# touch-switch-controller.net
KiCad netlist of a schematic drawn in EAGLE
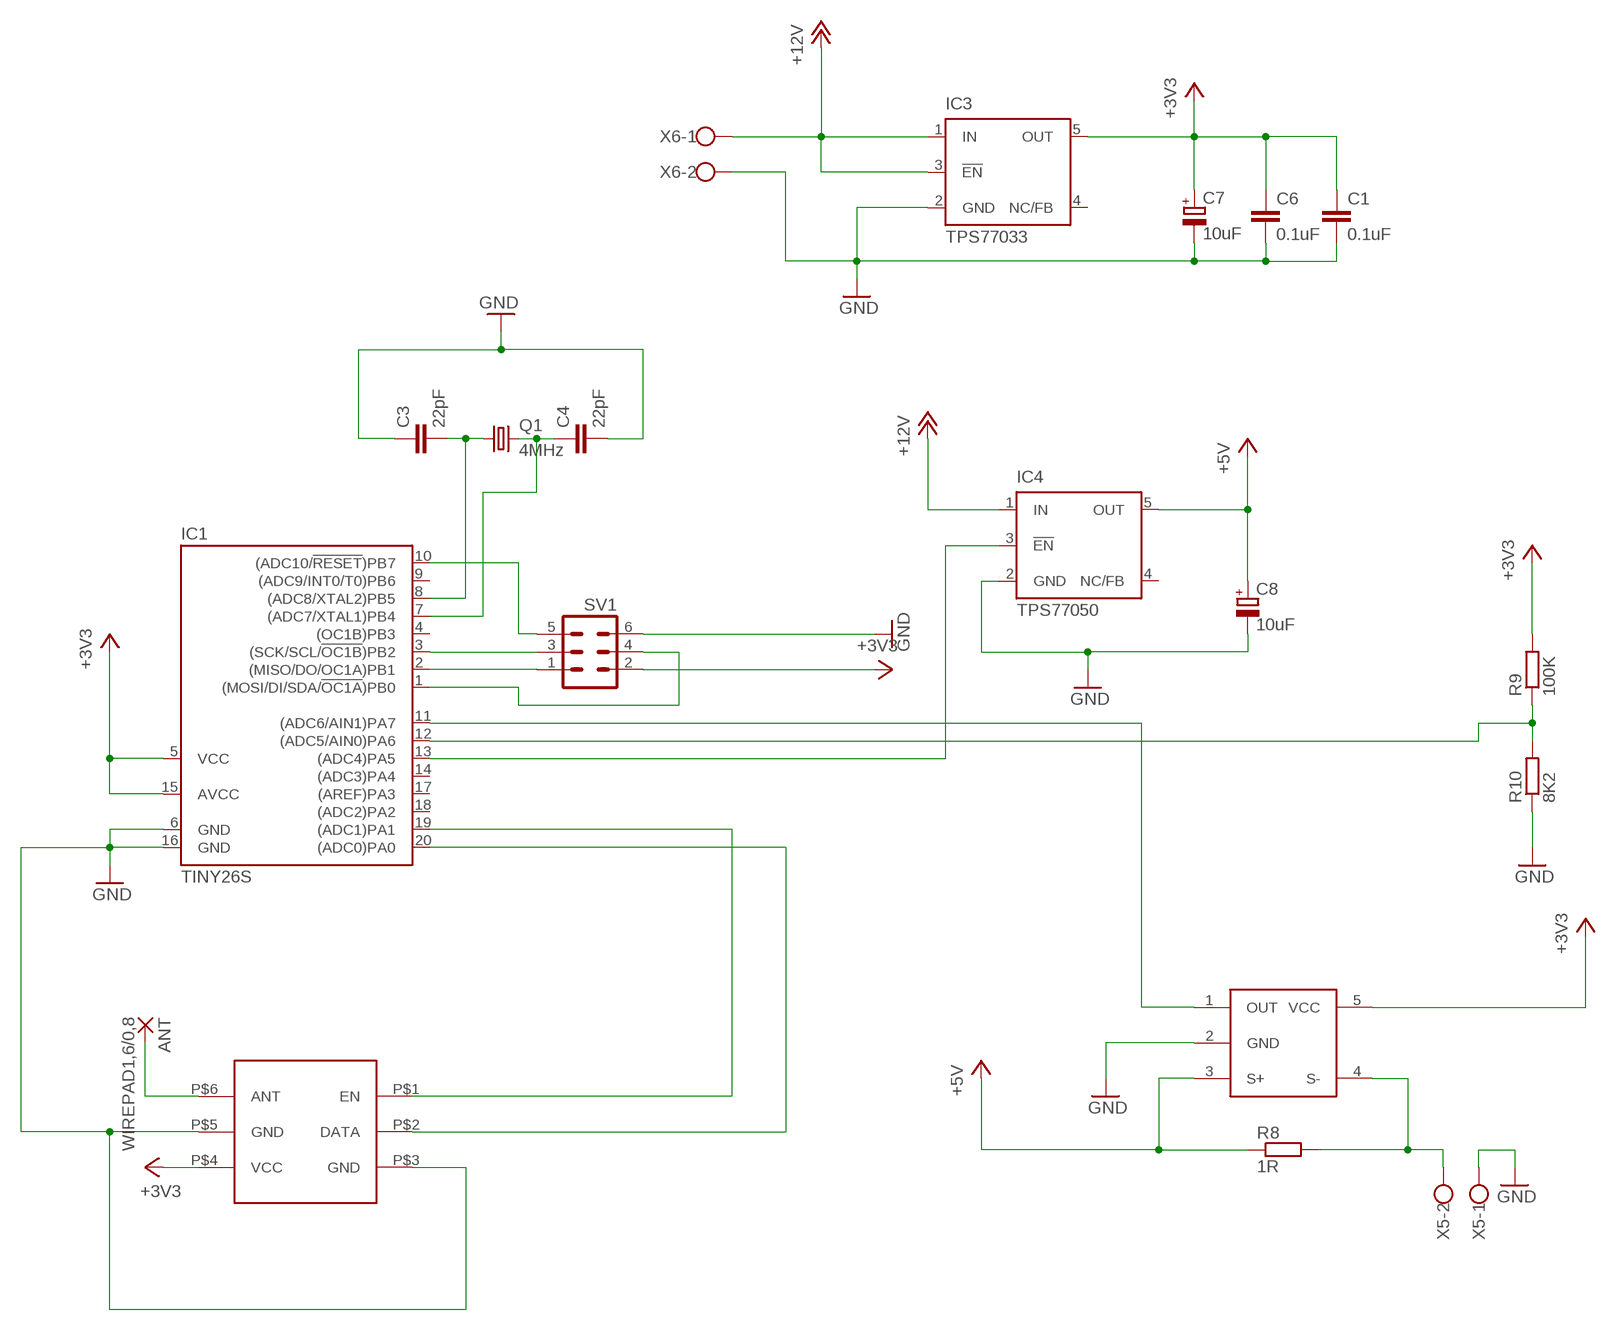
[diagram p0: schematic, sheet 1]

(export (version "E")
  (design (tool "Eeschema 10.0.6"))
  (components
    (comp (ref "ANT")
      (value "WIREPAD1,6/0,8")
      (footprint "eagle-import:1,6_0,8")
      (libsource (lib "eagle-import") (part "WIREPAD1,6/0,8"))
    )
    (comp (ref "C1")
      (value "0.1uF")
      (footprint "eagle-import:C0603")
      (libsource (lib "eagle-import") (part "C-EUC0603"))
    )
    (comp (ref "C3")
      (value "22pF")
      (footprint "eagle-import:C0603")
      (libsource (lib "eagle-import") (part "C-EUC0603"))
    )
    (comp (ref "C4")
      (value "22pF")
      (footprint "eagle-import:C0603")
      (libsource (lib "eagle-import") (part "C-EUC0603"))
    )
    (comp (ref "C6")
      (value "0.1uF")
      (footprint "eagle-import:C0603")
      (libsource (lib "eagle-import") (part "C-EUC0603"))
    )
    (comp (ref "C7")
      (value "10uF")
      (footprint "eagle-import:SMC_B")
      (libsource (lib "eagle-import") (part "CPOL-EUSMCB"))
    )
    (comp (ref "C8")
      (value "10uF")
      (footprint "eagle-import:SMC_B")
      (libsource (lib "eagle-import") (part "CPOL-EUSMCB"))
    )
    (comp (ref "IC1")
      (value "TINY26S")
      (footprint "eagle-import:SO20L")
      (fields (field (name "MPN") "ATTINY261-20SU"))
      (libsource (lib "eagle-import") (part "TINY26S"))
    )
    (comp (ref "IC3")
      (value "TPS77033")
      (footprint "eagle-import:SOT23-DBV")
      (fields (field (name "MF") "TEXAS INSTRUMENTS") (field (name "MPN") "TPS77033DBVT"))
      (libsource (lib "eagle-import") (part "TPS77033"))
    )
    (comp (ref "IC4")
      (value "TPS77050")
      (footprint "eagle-import:SOT23-DBV")
      (fields (field (name "MF") "TEXAS INSTRUMENT CONNECTORS") (field (name "MPN") "TPS77050DBVT"))
      (libsource (lib "eagle-import") (part "TPS77050"))
    )
    (comp (ref "Q1")
      (value "4MHz")
      (footprint "eagle-import:HC49UP")
      (libsource (lib "eagle-import") (part "CRYSTALHC49UP"))
    )
    (comp (ref "R8")
      (value "1R")
      (footprint "eagle-import:R0603")
      (libsource (lib "eagle-import") (part "R-EU_R0603"))
    )
    (comp (ref "R9")
      (value "100K")
      (footprint "eagle-import:R0603")
      (libsource (lib "eagle-import") (part "R-EU_R0603"))
    )
    (comp (ref "R10")
      (value "8K2")
      (footprint "eagle-import:R0603")
      (libsource (lib "eagle-import") (part "R-EU_R0603"))
    )
    (comp (ref "SV1")
      (value "MA03-2")
      (footprint "eagle-import:MA03-2")
      (libsource (lib "eagle-import") (part "MA03-2"))
    )
    (comp (ref "U$1")
      (value "ZXCT1086")
      (footprint "eagle-import:SOT23-5L")
      (libsource (lib "eagle-import") (part "ZXCT1086"))
    )
    (comp (ref "U$2")
      (value "RTFQ1")
      (footprint "eagle-import:RTFQ1")
      (libsource (lib "eagle-import") (part "RTFQ1"))
    )
    (comp (ref "X5")
      (value "W237-102")
      (footprint "eagle-import:W237-102")
      (fields (field (name "MPN") "237-102"))
      (libsource (lib "eagle-import") (part "W237-102"))
    )
    (comp (ref "X6")
      (value "W237-102")
      (footprint "eagle-import:W237-102")
      (fields (field (name "MPN") "237-102"))
      (libsource (lib "eagle-import") (part "W237-102"))
    )
  )
  (nets
    (net (code "1") (name "+3V3") (class "Default")
      (node (ref "C1") (pin "1") (pinfunction "1_1") (pintype "passive"))
      (node (ref "C6") (pin "1") (pinfunction "1_1") (pintype "passive"))
      (node (ref "C7") (pin "+") (pinfunction "+_+") (pintype "passive"))
      (node (ref "IC1") (pin "15") (pinfunction "AVCC_15") (pintype "power_in"))
      (node (ref "IC1") (pin "5") (pinfunction "VCC_5") (pintype "power_in"))
      (node (ref "IC3") (pin "5") (pinfunction "OUT_5") (pintype "passive"))
      (node (ref "R9") (pin "2") (pinfunction "2_2") (pintype "passive"))
      (node (ref "SV1") (pin "2") (pinfunction "2_2") (pintype "passive"))
      (node (ref "U$1") (pin "5") (pinfunction "VCC_5") (pintype "bidirectional"))
      (node (ref "U$2") (pin "P$4") (pinfunction "VCC_P$4") (pintype "bidirectional"))
    )
    (net (code "2") (name "+5V") (class "Default")
      (node (ref "C8") (pin "+") (pinfunction "+_+") (pintype "passive"))
      (node (ref "IC4") (pin "5") (pinfunction "OUT_5") (pintype "passive"))
      (node (ref "R8") (pin "1") (pinfunction "1_1") (pintype "passive"))
      (node (ref "U$1") (pin "3") (pinfunction "S+_3") (pintype "bidirectional"))
    )
    (net (code "3") (name "+12V") (class "Default")
      (node (ref "IC3") (pin "1") (pinfunction "IN_1") (pintype "input"))
      (node (ref "IC3") (pin "3") (pinfunction "~{EN}_3") (pintype "input"))
      (node (ref "IC4") (pin "1") (pinfunction "IN_1") (pintype "input"))
      (node (ref "X6") (pin "1") (pinfunction "KL_1") (pintype "passive"))
    )
    (net (code "4") (name "GND") (class "Default")
      (node (ref "C1") (pin "2") (pinfunction "2_2") (pintype "passive"))
      (node (ref "C3") (pin "1") (pinfunction "1_1") (pintype "passive"))
      (node (ref "C4") (pin "2") (pinfunction "2_2") (pintype "passive"))
      (node (ref "C6") (pin "2") (pinfunction "2_2") (pintype "passive"))
      (node (ref "C7") (pin "-") (pinfunction "-_-") (pintype "passive"))
      (node (ref "C8") (pin "-") (pinfunction "-_-") (pintype "passive"))
      (node (ref "IC1") (pin "16") (pinfunction "GND_16") (pintype "power_in"))
      (node (ref "IC1") (pin "6") (pinfunction "GND_6") (pintype "power_in"))
      (node (ref "IC3") (pin "2") (pinfunction "GND_2") (pintype "power_in"))
      (node (ref "IC4") (pin "2") (pinfunction "GND_2") (pintype "power_in"))
      (node (ref "R10") (pin "1") (pinfunction "1_1") (pintype "passive"))
      (node (ref "SV1") (pin "6") (pinfunction "6_6") (pintype "passive"))
      (node (ref "U$1") (pin "2") (pinfunction "GND_2") (pintype "bidirectional"))
      (node (ref "U$2") (pin "P$3") (pinfunction "GND_P$3") (pintype "bidirectional"))
      (node (ref "U$2") (pin "P$5") (pinfunction "GND_P$5") (pintype "bidirectional"))
      (node (ref "X5") (pin "1") (pinfunction "KL_1") (pintype "passive"))
      (node (ref "X6") (pin "2") (pinfunction "KL_2") (pintype "passive"))
    )
    (net (code "5") (name "Net-(ANT-P)") (class "Default")
      (node (ref "ANT") (pin "1") (pinfunction "P_1") (pintype "passive"))
      (node (ref "U$2") (pin "P$6") (pinfunction "ANT_P$6") (pintype "bidirectional"))
    )
    (net (code "6") (name "Net-(IC1-(ADC0)PA0)") (class "Default")
      (node (ref "IC1") (pin "20") (pinfunction "(ADC0)PA0_20") (pintype "bidirectional"))
      (node (ref "U$2") (pin "P$2") (pinfunction "DATA_P$2") (pintype "bidirectional"))
    )
    (net (code "7") (name "Net-(IC1-(ADC1)PA1)") (class "Default")
      (node (ref "IC1") (pin "19") (pinfunction "(ADC1)PA1_19") (pintype "bidirectional"))
      (node (ref "U$2") (pin "P$1") (pinfunction "EN_P$1") (pintype "bidirectional"))
    )
    (net (code "8") (name "Net-(IC1-(ADC4)PA5)") (class "Default")
      (node (ref "IC1") (pin "13") (pinfunction "(ADC4)PA5_13") (pintype "bidirectional"))
      (node (ref "IC4") (pin "3") (pinfunction "~{EN}_3") (pintype "input"))
    )
    (net (code "9") (name "Net-(IC1-(ADC5{slash}AIN0)PA6)") (class "Default")
      (node (ref "IC1") (pin "12") (pinfunction "(ADC5/AIN0)PA6_12") (pintype "bidirectional"))
      (node (ref "R10") (pin "2") (pinfunction "2_2") (pintype "passive"))
      (node (ref "R9") (pin "1") (pinfunction "1_1") (pintype "passive"))
    )
    (net (code "10") (name "Net-(IC1-(ADC6{slash}AIN1)PA7)") (class "Default")
      (node (ref "IC1") (pin "11") (pinfunction "(ADC6/AIN1)PA7_11") (pintype "bidirectional"))
      (node (ref "U$1") (pin "1") (pinfunction "OUT_1") (pintype "bidirectional"))
    )
    (net (code "11") (name "Net-(IC1-(ADC7{slash}XTAL1)PB4)") (class "Default")
      (node (ref "C4") (pin "1") (pinfunction "1_1") (pintype "passive"))
      (node (ref "IC1") (pin "7") (pinfunction "(ADC7/XTAL1)PB4_7") (pintype "bidirectional"))
      (node (ref "Q1") (pin "2") (pinfunction "2_2") (pintype "passive"))
    )
    (net (code "12") (name "Net-(IC1-(ADC8{slash}XTAL2)PB5)") (class "Default")
      (node (ref "C3") (pin "2") (pinfunction "2_2") (pintype "passive"))
      (node (ref "IC1") (pin "8") (pinfunction "(ADC8/XTAL2)PB5_8") (pintype "bidirectional"))
      (node (ref "Q1") (pin "1") (pinfunction "1_1") (pintype "passive"))
    )
    (net (code "13") (name "Net-(IC1-(ADC10{slash}~{RESET})PB7)") (class "Default")
      (node (ref "IC1") (pin "10") (pinfunction "(ADC10/~{RESET})PB7_10") (pintype "bidirectional"))
      (node (ref "SV1") (pin "5") (pinfunction "5_5") (pintype "passive"))
    )
    (net (code "14") (name "Net-(IC1-(MISO{slash}DO{slash}OC1A)PB1)") (class "Default")
      (node (ref "IC1") (pin "2") (pinfunction "(MISO/DO/OC1A)PB1_2") (pintype "bidirectional"))
      (node (ref "SV1") (pin "1") (pinfunction "1_1") (pintype "passive"))
    )
    (net (code "15") (name "Net-(IC1-(MOSI{slash}DI{slash}SDA{slash}~{OC1A})PB0)") (class "Default")
      (node (ref "IC1") (pin "1") (pinfunction "(MOSI/DI/SDA/~{OC1A})PB0_1") (pintype "bidirectional"))
      (node (ref "SV1") (pin "4") (pinfunction "4_4") (pintype "passive"))
    )
    (net (code "16") (name "Net-(IC1-(SCK{slash}SCL{slash}~{OC1B})PB2)") (class "Default")
      (node (ref "IC1") (pin "3") (pinfunction "(SCK/SCL/~{OC1B})PB2_3") (pintype "bidirectional"))
      (node (ref "SV1") (pin "3") (pinfunction "3_3") (pintype "passive"))
    )
    (net (code "17") (name "Net-(U$1-S-)") (class "Default")
      (node (ref "R8") (pin "2") (pinfunction "2_2") (pintype "passive"))
      (node (ref "U$1") (pin "4") (pinfunction "S-_4") (pintype "bidirectional"))
      (node (ref "X5") (pin "2") (pinfunction "KL_2") (pintype "passive"))
    )
    (net (code "18") (name "unconnected-(IC1-(ADC2)PA2-Pad18)") (class "Default")
      (node (ref "IC1") (pin "18") (pinfunction "(ADC2)PA2_18") (pintype "bidirectional"))
    )
    (net (code "19") (name "unconnected-(IC1-(ADC3)PA4-Pad14)") (class "Default")
      (node (ref "IC1") (pin "14") (pinfunction "(ADC3)PA4_14") (pintype "bidirectional"))
    )
    (net (code "20") (name "unconnected-(IC1-(ADC9{slash}INT0{slash}T0)PB6-Pad9)") (class "Default")
      (node (ref "IC1") (pin "9") (pinfunction "(ADC9/INT0/T0)PB6_9") (pintype "bidirectional"))
    )
    (net (code "21") (name "unconnected-(IC1-(AREF)PA3-Pad17)") (class "Default")
      (node (ref "IC1") (pin "17") (pinfunction "(AREF)PA3_17") (pintype "bidirectional"))
    )
    (net (code "22") (name "unconnected-(IC1-(OC1B)PB3-Pad4)") (class "Default")
      (node (ref "IC1") (pin "4") (pinfunction "(OC1B)PB3_4") (pintype "bidirectional"))
    )
    (net (code "23") (name "unconnected-(IC3-NC{slash}FB-Pad4)") (class "Default")
      (node (ref "IC3") (pin "4") (pinfunction "NC/FB_4") (pintype "passive"))
    )
    (net (code "24") (name "unconnected-(IC4-NC{slash}FB-Pad4)") (class "Default")
      (node (ref "IC4") (pin "4") (pinfunction "NC/FB_4") (pintype "passive"))
    )
  )
)
